# Signal.net
KiCad netlist of a schematic drawn in Altium Designer
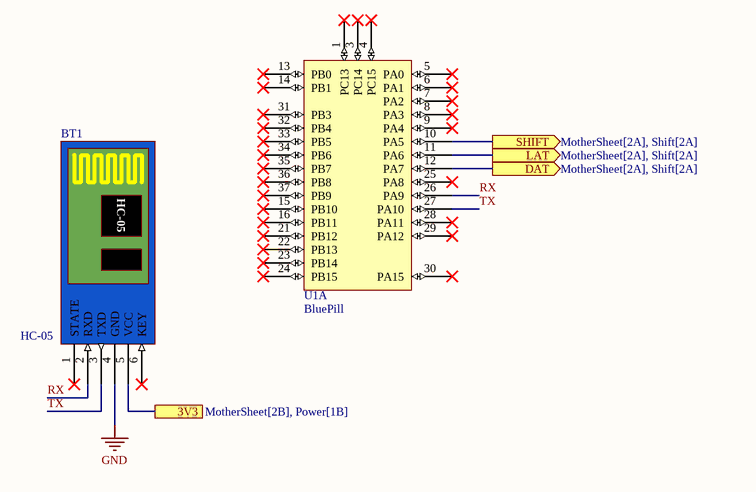
[diagram p0: Signal.SchDoc]

(export (version "E")
  (design (tool "Eeschema 10.0.6"))
  (components
    (comp (ref "BT1")
      (value "HC-05")
      (footprint "HC-05")
      (libsource (lib "LaBibliothequeDeLongNhong") (part "HC-05"))
    )
    (comp (ref "U1")
      (value "BluePill")
      (footprint "BluePill")
      (libsource (lib "LaBibliothequeDeLongNhong") (part "BluePill"))
    )
  )
  (nets
    (net (code "1") (name "/3V3") (class "Default")
      (node (ref "BT1") (pin "5") (pinfunction "VCC_5") (pintype "power_in"))
    )
    (net (code "2") (name "/DAT") (class "Default")
      (node (ref "U1") (pin "12") (pinfunction "PA7_12") (pintype "bidirectional"))
    )
    (net (code "3") (name "/LAT") (class "Default")
      (node (ref "U1") (pin "11") (pinfunction "PA6_11") (pintype "bidirectional"))
    )
    (net (code "4") (name "/RX") (class "Default")
      (node (ref "BT1") (pin "2") (pinfunction "RXD_2") (pintype "input"))
      (node (ref "U1") (pin "26") (pinfunction "PA9_26") (pintype "bidirectional"))
    )
    (net (code "5") (name "/SHIFT") (class "Default")
      (node (ref "U1") (pin "10") (pinfunction "PA5_10") (pintype "bidirectional"))
    )
    (net (code "6") (name "/TX") (class "Default")
      (node (ref "BT1") (pin "3") (pinfunction "TXD_3") (pintype "output"))
      (node (ref "U1") (pin "27") (pinfunction "PA10_27") (pintype "bidirectional"))
    )
    (net (code "7") (name "GND") (class "Default")
      (node (ref "BT1") (pin "4") (pinfunction "GND_4") (pintype "power_in"))
    )
    (net (code "8") (name "unconnected-(BT1-KEY-Pad6)") (class "Default")
      (node (ref "BT1") (pin "6") (pinfunction "KEY_6") (pintype "input+no_connect"))
    )
    (net (code "9") (name "unconnected-(BT1-STATE-Pad1)") (class "Default")
      (node (ref "BT1") (pin "1") (pinfunction "STATE_1") (pintype "passive+no_connect"))
    )
    (net (code "10") (name "unconnected-(U1A-PA0-Pad5)") (class "Default")
      (node (ref "U1") (pin "5") (pinfunction "PA0_5") (pintype "bidirectional+no_connect"))
    )
    (net (code "11") (name "unconnected-(U1A-PA1-Pad6)") (class "Default")
      (node (ref "U1") (pin "6") (pinfunction "PA1_6") (pintype "bidirectional+no_connect"))
    )
    (net (code "12") (name "unconnected-(U1A-PA2-Pad7)") (class "Default")
      (node (ref "U1") (pin "7") (pinfunction "PA2_7") (pintype "bidirectional+no_connect"))
    )
    (net (code "13") (name "unconnected-(U1A-PA3-Pad8)") (class "Default")
      (node (ref "U1") (pin "8") (pinfunction "PA3_8") (pintype "bidirectional+no_connect"))
    )
    (net (code "14") (name "unconnected-(U1A-PA4-Pad9)") (class "Default")
      (node (ref "U1") (pin "9") (pinfunction "PA4_9") (pintype "bidirectional+no_connect"))
    )
    (net (code "15") (name "unconnected-(U1A-PA8-Pad25)") (class "Default")
      (node (ref "U1") (pin "25") (pinfunction "PA8_25") (pintype "bidirectional+no_connect"))
    )
    (net (code "16") (name "unconnected-(U1A-PA11-Pad28)") (class "Default")
      (node (ref "U1") (pin "28") (pinfunction "PA11_28") (pintype "bidirectional+no_connect"))
    )
    (net (code "17") (name "unconnected-(U1A-PA12-Pad29)") (class "Default")
      (node (ref "U1") (pin "29") (pinfunction "PA12_29") (pintype "bidirectional+no_connect"))
    )
    (net (code "18") (name "unconnected-(U1A-PA15-Pad30)") (class "Default")
      (node (ref "U1") (pin "30") (pinfunction "PA15_30") (pintype "bidirectional+no_connect"))
    )
    (net (code "19") (name "unconnected-(U1A-PB0-Pad13)") (class "Default")
      (node (ref "U1") (pin "13") (pinfunction "PB0_13") (pintype "bidirectional+no_connect"))
    )
    (net (code "20") (name "unconnected-(U1A-PB1-Pad14)") (class "Default")
      (node (ref "U1") (pin "14") (pinfunction "PB1_14") (pintype "bidirectional+no_connect"))
    )
    (net (code "21") (name "unconnected-(U1A-PB3-Pad31)") (class "Default")
      (node (ref "U1") (pin "31") (pinfunction "PB3_31") (pintype "bidirectional+no_connect"))
    )
    (net (code "22") (name "unconnected-(U1A-PB4-Pad32)") (class "Default")
      (node (ref "U1") (pin "32") (pinfunction "PB4_32") (pintype "bidirectional+no_connect"))
    )
    (net (code "23") (name "unconnected-(U1A-PB5-Pad33)") (class "Default")
      (node (ref "U1") (pin "33") (pinfunction "PB5_33") (pintype "bidirectional+no_connect"))
    )
    (net (code "24") (name "unconnected-(U1A-PB6-Pad34)") (class "Default")
      (node (ref "U1") (pin "34") (pinfunction "PB6_34") (pintype "bidirectional+no_connect"))
    )
    (net (code "25") (name "unconnected-(U1A-PB7-Pad35)") (class "Default")
      (node (ref "U1") (pin "35") (pinfunction "PB7_35") (pintype "bidirectional+no_connect"))
    )
    (net (code "26") (name "unconnected-(U1A-PB8-Pad36)") (class "Default")
      (node (ref "U1") (pin "36") (pinfunction "PB8_36") (pintype "bidirectional+no_connect"))
    )
    (net (code "27") (name "unconnected-(U1A-PB9-Pad37)") (class "Default")
      (node (ref "U1") (pin "37") (pinfunction "PB9_37") (pintype "bidirectional+no_connect"))
    )
    (net (code "28") (name "unconnected-(U1A-PB10-Pad15)") (class "Default")
      (node (ref "U1") (pin "15") (pinfunction "PB10_15") (pintype "bidirectional+no_connect"))
    )
    (net (code "29") (name "unconnected-(U1A-PB11-Pad16)") (class "Default")
      (node (ref "U1") (pin "16") (pinfunction "PB11_16") (pintype "bidirectional+no_connect"))
    )
    (net (code "30") (name "unconnected-(U1A-PB12-Pad21)") (class "Default")
      (node (ref "U1") (pin "21") (pinfunction "PB12_21") (pintype "bidirectional+no_connect"))
    )
    (net (code "31") (name "unconnected-(U1A-PB13-Pad22)") (class "Default")
      (node (ref "U1") (pin "22") (pinfunction "PB13_22") (pintype "bidirectional+no_connect"))
    )
    (net (code "32") (name "unconnected-(U1A-PB14-Pad23)") (class "Default")
      (node (ref "U1") (pin "23") (pinfunction "PB14_23") (pintype "bidirectional+no_connect"))
    )
    (net (code "33") (name "unconnected-(U1A-PB15-Pad24)") (class "Default")
      (node (ref "U1") (pin "24") (pinfunction "PB15_24") (pintype "bidirectional+no_connect"))
    )
    (net (code "34") (name "unconnected-(U1A-PC13-Pad1)") (class "Default")
      (node (ref "U1") (pin "1") (pinfunction "PC13_1") (pintype "bidirectional+no_connect"))
    )
    (net (code "35") (name "unconnected-(U1A-PC14-Pad3)") (class "Default")
      (node (ref "U1") (pin "3") (pinfunction "PC14_3") (pintype "bidirectional+no_connect"))
    )
    (net (code "36") (name "unconnected-(U1A-PC15-Pad4)") (class "Default")
      (node (ref "U1") (pin "4") (pinfunction "PC15_4") (pintype "bidirectional+no_connect"))
    )
  )
)
